# Sheet1.net
KiCad netlist of a schematic drawn in Altium Designer
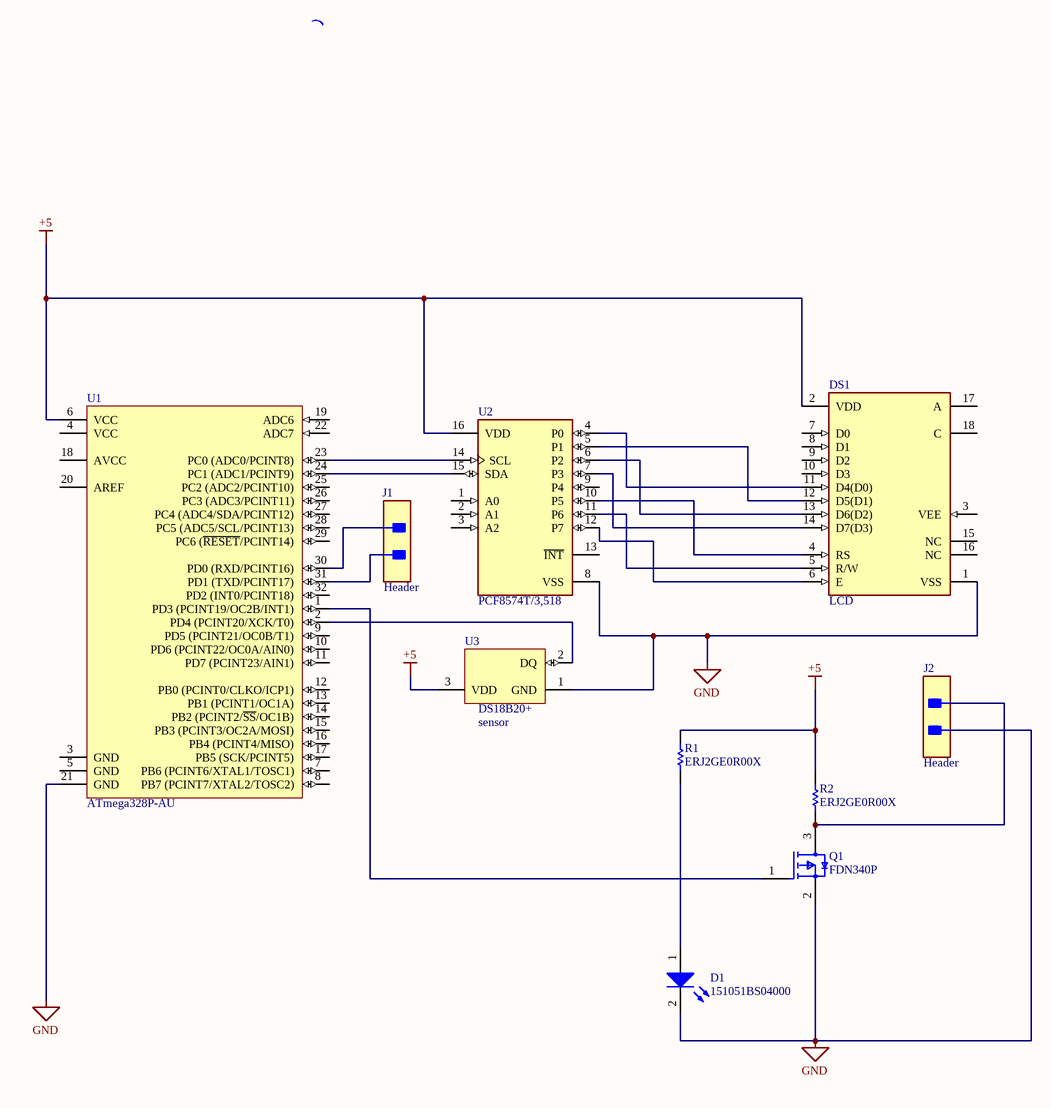
[diagram p0: Sheet1.SchDoc]

(export (version "E")
  (design (tool "Eeschema 10.0.6"))
  (components
    (comp (ref "D1")
      (value "151051BS04000")
      (footprint "WL-TMRC_D5.9H8.7")
      (libsource (lib "Altium Content Vault") (part "LED_Blue_1A-2K"))
    )
    (comp (ref "DS1")
      (value "LCD")
      (footprint "FP-EA_DIP162-DHNLED-MFG")
      (description "LCD MOD CHAR 2X16 Y/G BACKLIT")
      (fields
        (field (name "MANUFACTURER PART NUMBER") "EA DIP162-DHNLED")
        (field (name "MANUFACTURER") "Display Visions")
      )
      (libsource (lib "Altium Content Vault") (part "d15ad439837a3ed901fb7cfc26901aa"))
    )
    (comp (ref "J1")
      (value "Header")
      (footprint "FP-SYP-02T-1-MFG")
      (description "CONN PLUG HSNG 2POS 2.5MM RED")
      (libsource (lib "") (part "31f24ba94ab9d7f7090826e91f45e53_1"))
    )
    (comp (ref "J2")
      (value "Header")
      (footprint "FP-SYP-02T-1-MFG")
      (description "CONN PLUG HSNG 2POS 2.5MM RED")
      (libsource (lib "Altium Content Vault") (part "31f24ba94ab9d7f7090826e91f45e53"))
    )
    (comp (ref "Q1")
      (value "FDN340P")
      (footprint "FP-527AG-MFG")
      (description "MOSFET P-CH 20V 2A SSOT3")
      (libsource (lib "Altium Content Vault") (part "d23f43cc42f60b967b7caccf14518fd"))
    )
    (comp (ref "R1")
      (value "ERJ2GE0R00X")
      (footprint "RESC1005X40X25LL05T05")
      (description "Chip Resistor, 0 Ohm, 0.1 W, -55 to 155 degC, 0402 (1005 Metric), RoHS, Tape and Reel")
      (fields (field (name "MANUFACTURER") "Panasonic") (field (name "TOLERANCE") "5%"))
      (libsource (lib "Altium Content Vault") (part "RES-2"))
    )
    (comp (ref "R2")
      (value "ERJ2GE0R00X")
      (footprint "RESC1005X40X25LL05T05")
      (description "Chip Resistor, 0 Ohm, 0.1 W, -55 to 155 degC, 0402 (1005 Metric), RoHS, Tape and Reel")
      (fields (field (name "MANUFACTURER") "Panasonic") (field (name "TOLERANCE") "5%"))
      (libsource (lib "Altium Content Vault") (part "RES-2"))
    )
    (comp (ref "U1")
      (value "ATmega328P-AU")
      (footprint "32A_M")
      (libsource (lib "Altium Content Vault") (part "MC-8B-ATM48-SQ32"))
    )
    (comp (ref "U2")
      (value "PCF8574T/3,518")
      (footprint "FP-SOT162-1-MFG")
      (description "IC I/O EXPANDER I2C 8B 16SOIC")
      (fields
        (field (name "MANUFACTURER") "NXP Semiconductors")
        (field (name "OCTOPART") "https://octopart.com/pcf8574t%2F3%2C518-nxp+semiconductors-10470852")
      )
      (libsource (lib "Altium Content Vault") (part "f7fde53ce59de981fb0b266a4e103eb"))
    )
    (comp (ref "U3")
      (value "DS18B20+")
      (footprint "Q3+1")
      (libsource (lib "Altium Content Vault") (part "SEN-TEMP-DS1821-SIL3"))
    )
  )
  (nets
    (net (code "1") (name "+5") (class "Default")
      (node (ref "DS1") (pin "2") (pinfunction "VDD_2") (pintype "power_in"))
      (node (ref "R1") (pin "2") (pinfunction "2_2") (pintype "passive"))
      (node (ref "R2") (pin "2") (pinfunction "2_2") (pintype "passive"))
      (node (ref "U1") (pin "6") (pinfunction "VCC_6") (pintype "power_in"))
      (node (ref "U2") (pin "16") (pinfunction "VDD_16") (pintype "power_in"))
      (node (ref "U3") (pin "3") (pinfunction "VDD_3") (pintype "power_in"))
    )
    (net (code "2") (name "GND") (class "Default")
      (node (ref "D1") (pin "2") (pinfunction "K_2") (pintype "passive"))
      (node (ref "DS1") (pin "1") (pinfunction "VSS_1") (pintype "power_in"))
      (node (ref "Q1") (pin "2") (pinfunction "S_2") (pintype "passive"))
      (node (ref "U1") (pin "21") (pinfunction "GND_21") (pintype "power_in"))
      (node (ref "U2") (pin "8") (pinfunction "VSS_8") (pintype "power_in"))
      (node (ref "U3") (pin "1") (pinfunction "GND_1") (pintype "power_in"))
    )
    (net (code "3") (name "Net-(D1-A)") (class "Default")
      (node (ref "D1") (pin "1") (pinfunction "A_1") (pintype "passive"))
      (node (ref "R1") (pin "1") (pinfunction "1_1") (pintype "passive"))
    )
    (net (code "4") (name "Net-(DS1-D4(D0))") (class "Default")
      (node (ref "DS1") (pin "11") (pinfunction "D4(D0)_11") (pintype "input"))
      (node (ref "U2") (pin "4") (pinfunction "P0_4") (pintype "bidirectional"))
    )
    (net (code "5") (name "Net-(DS1-D5(D1))") (class "Default")
      (node (ref "DS1") (pin "12") (pinfunction "D5(D1)_12") (pintype "input"))
      (node (ref "U2") (pin "5") (pinfunction "P1_5") (pintype "bidirectional"))
    )
    (net (code "6") (name "Net-(DS1-D6(D2))") (class "Default")
      (node (ref "DS1") (pin "13") (pinfunction "D6(D2)_13") (pintype "input"))
      (node (ref "U2") (pin "6") (pinfunction "P2_6") (pintype "bidirectional"))
    )
    (net (code "7") (name "Net-(DS1-D7(D3))") (class "Default")
      (node (ref "DS1") (pin "14") (pinfunction "D7(D3)_14") (pintype "input"))
      (node (ref "U2") (pin "7") (pinfunction "P3_7") (pintype "bidirectional"))
    )
    (net (code "8") (name "Net-(DS1-E)") (class "Default")
      (node (ref "DS1") (pin "6") (pinfunction "E_6") (pintype "input"))
      (node (ref "U2") (pin "12") (pinfunction "P7_12") (pintype "bidirectional"))
    )
    (net (code "9") (name "Net-(DS1-RS)") (class "Default")
      (node (ref "DS1") (pin "4") (pinfunction "RS_4") (pintype "input"))
      (node (ref "U2") (pin "10") (pinfunction "P5_10") (pintype "bidirectional"))
    )
    (net (code "10") (name "Net-(DS1-R{slash}W)") (class "Default")
      (node (ref "DS1") (pin "5") (pinfunction "R/W_5") (pintype "input"))
      (node (ref "U2") (pin "11") (pinfunction "P6_11") (pintype "bidirectional"))
    )
    (net (code "11") (name "Net-(Q1-D)") (class "Default")
      (node (ref "Q1") (pin "3") (pinfunction "D_3") (pintype "passive"))
      (node (ref "R2") (pin "1") (pinfunction "1_1") (pintype "passive"))
    )
    (net (code "12") (name "Net-(Q1-G)") (class "Default")
      (node (ref "Q1") (pin "1") (pinfunction "G_1") (pintype "passive"))
      (node (ref "U1") (pin "1") (pinfunction "PD3_(PCINT19/OC2B/INT1)_1") (pintype "bidirectional"))
    )
    (net (code "13") (name "Net-(U1-PC0_(ADC0{slash}PCINT8))") (class "Default")
      (node (ref "U1") (pin "23") (pinfunction "PC0_(ADC0/PCINT8)_23") (pintype "bidirectional"))
      (node (ref "U2") (pin "14") (pinfunction "SCL_14") (pintype "input"))
    )
    (net (code "14") (name "Net-(U1-PC1_(ADC1{slash}PCINT9))") (class "Default")
      (node (ref "U1") (pin "24") (pinfunction "PC1_(ADC1/PCINT9)_24") (pintype "bidirectional"))
      (node (ref "U2") (pin "15") (pinfunction "SDA_15") (pintype "bidirectional"))
    )
    (net (code "15") (name "Net-(U1-PD4_(PCINT20{slash}XCK{slash}T0))") (class "Default")
      (node (ref "U1") (pin "2") (pinfunction "PD4_(PCINT20/XCK/T0)_2") (pintype "bidirectional"))
      (node (ref "U3") (pin "2") (pinfunction "DQ_2") (pintype "bidirectional"))
    )
    (net (code "16") (name "unconnected-(DS1-A-Pad17)") (class "Default")
      (node (ref "DS1") (pin "17") (pinfunction "A_17") (pintype "passive"))
    )
    (net (code "17") (name "unconnected-(DS1-C-Pad18)") (class "Default")
      (node (ref "DS1") (pin "18") (pinfunction "C_18") (pintype "passive"))
    )
    (net (code "18") (name "unconnected-(DS1-D0-Pad7)") (class "Default")
      (node (ref "DS1") (pin "7") (pinfunction "D0_7") (pintype "input"))
    )
    (net (code "19") (name "unconnected-(DS1-D1-Pad8)") (class "Default")
      (node (ref "DS1") (pin "8") (pinfunction "D1_8") (pintype "input"))
    )
    (net (code "20") (name "unconnected-(DS1-D2-Pad9)") (class "Default")
      (node (ref "DS1") (pin "9") (pinfunction "D2_9") (pintype "input"))
    )
    (net (code "21") (name "unconnected-(DS1-D3-Pad10)") (class "Default")
      (node (ref "DS1") (pin "10") (pinfunction "D3_10") (pintype "input"))
    )
    (net (code "22") (name "unconnected-(DS1-NC-Pad15)") (class "Default")
      (node (ref "DS1") (pin "15") (pinfunction "NC_15") (pintype "passive"))
    )
    (net (code "23") (name "unconnected-(DS1-NC-Pad16)") (class "Default")
      (node (ref "DS1") (pin "16") (pinfunction "NC_16") (pintype "passive"))
    )
    (net (code "24") (name "unconnected-(DS1-VEE-Pad3)") (class "Default")
      (node (ref "DS1") (pin "3") (pinfunction "VEE_3") (pintype "input"))
    )
    (net (code "25") (name "unconnected-(U1-ADC6-Pad19)") (class "Default")
      (node (ref "U1") (pin "19") (pinfunction "ADC6_19") (pintype "input"))
    )
    (net (code "26") (name "unconnected-(U1-ADC7-Pad22)") (class "Default")
      (node (ref "U1") (pin "22") (pinfunction "ADC7_22") (pintype "input"))
    )
    (net (code "27") (name "unconnected-(U1-AREF-Pad20)") (class "Default")
      (node (ref "U1") (pin "20") (pinfunction "AREF_20") (pintype "passive"))
    )
    (net (code "28") (name "unconnected-(U1-AVCC-Pad18)") (class "Default")
      (node (ref "U1") (pin "18") (pinfunction "AVCC_18") (pintype "power_in"))
    )
    (net (code "29") (name "unconnected-(U1-GND-Pad3)") (class "Default")
      (node (ref "U1") (pin "3") (pinfunction "GND_3") (pintype "power_in"))
    )
    (net (code "30") (name "unconnected-(U1-GND-Pad5)") (class "Default")
      (node (ref "U1") (pin "5") (pinfunction "GND_5") (pintype "power_in"))
    )
    (net (code "31") (name "unconnected-(U1-PB0_(PCINT0{slash}CLKO{slash}ICP1)-Pad12)") (class "Default")
      (node (ref "U1") (pin "12") (pinfunction "PB0_(PCINT0/CLKO/ICP1)_12") (pintype "bidirectional"))
    )
    (net (code "32") (name "unconnected-(U1-PB1_(PCINT1{slash}OC1A)-Pad13)") (class "Default")
      (node (ref "U1") (pin "13") (pinfunction "PB1_(PCINT1/OC1A)_13") (pintype "bidirectional"))
    )
    (net (code "33") (name "unconnected-(U1-PB2_(PCINT2{slash}~{SS}{slash}OC1B)-Pad14)") (class "Default")
      (node (ref "U1") (pin "14") (pinfunction "PB2_(PCINT2/~{SS}/OC1B)_14") (pintype "bidirectional"))
    )
    (net (code "34") (name "unconnected-(U1-PB3_(PCINT3{slash}OC2A{slash}MOSI)-Pad15)") (class "Default")
      (node (ref "U1") (pin "15") (pinfunction "PB3_(PCINT3/OC2A/MOSI)_15") (pintype "bidirectional"))
    )
    (net (code "35") (name "unconnected-(U1-PB4_(PCINT4{slash}MISO)-Pad16)") (class "Default")
      (node (ref "U1") (pin "16") (pinfunction "PB4_(PCINT4/MISO)_16") (pintype "bidirectional"))
    )
    (net (code "36") (name "unconnected-(U1-PB5_(SCK{slash}PCINT5)-Pad17)") (class "Default")
      (node (ref "U1") (pin "17") (pinfunction "PB5_(SCK/PCINT5)_17") (pintype "bidirectional"))
    )
    (net (code "37") (name "unconnected-(U1-PB6_(PCINT6{slash}XTAL1{slash}TOSC1)-Pad7)") (class "Default")
      (node (ref "U1") (pin "7") (pinfunction "PB6_(PCINT6/XTAL1/TOSC1)_7") (pintype "bidirectional"))
    )
    (net (code "38") (name "unconnected-(U1-PB7_(PCINT7{slash}XTAL2{slash}TOSC2)-Pad8)") (class "Default")
      (node (ref "U1") (pin "8") (pinfunction "PB7_(PCINT7/XTAL2/TOSC2)_8") (pintype "bidirectional"))
    )
    (net (code "39") (name "unconnected-(U1-PC2_(ADC2{slash}PCINT10)-Pad25)") (class "Default")
      (node (ref "U1") (pin "25") (pinfunction "PC2_(ADC2/PCINT10)_25") (pintype "bidirectional"))
    )
    (net (code "40") (name "unconnected-(U1-PC3_(ADC3{slash}PCINT11)-Pad26)") (class "Default")
      (node (ref "U1") (pin "26") (pinfunction "PC3_(ADC3/PCINT11)_26") (pintype "bidirectional"))
    )
    (net (code "41") (name "unconnected-(U1-PC4_(ADC4{slash}SDA{slash}PCINT12)-Pad27)") (class "Default")
      (node (ref "U1") (pin "27") (pinfunction "PC4_(ADC4/SDA/PCINT12)_27") (pintype "bidirectional"))
    )
    (net (code "42") (name "unconnected-(U1-PC5_(ADC5{slash}SCL{slash}PCINT13)-Pad28)") (class "Default")
      (node (ref "U1") (pin "28") (pinfunction "PC5_(ADC5/SCL/PCINT13)_28") (pintype "bidirectional"))
    )
    (net (code "43") (name "unconnected-(U1-PC6_(~{RESET}{slash}PCINT14)-Pad29)") (class "Default")
      (node (ref "U1") (pin "29") (pinfunction "PC6_(~{RESET}/PCINT14)_29") (pintype "bidirectional"))
    )
    (net (code "44") (name "unconnected-(U1-PD0_(RXD{slash}PCINT16)-Pad30)") (class "Default")
      (node (ref "U1") (pin "30") (pinfunction "PD0_(RXD/PCINT16)_30") (pintype "bidirectional"))
    )
    (net (code "45") (name "unconnected-(U1-PD1_(TXD{slash}PCINT17)-Pad31)") (class "Default")
      (node (ref "U1") (pin "31") (pinfunction "PD1_(TXD/PCINT17)_31") (pintype "bidirectional"))
    )
    (net (code "46") (name "unconnected-(U1-PD2_(INT0{slash}PCINT18)-Pad32)") (class "Default")
      (node (ref "U1") (pin "32") (pinfunction "PD2_(INT0/PCINT18)_32") (pintype "bidirectional"))
    )
    (net (code "47") (name "unconnected-(U1-PD5_(PCINT21{slash}OC0B{slash}T1)-Pad9)") (class "Default")
      (node (ref "U1") (pin "9") (pinfunction "PD5_(PCINT21/OC0B/T1)_9") (pintype "bidirectional"))
    )
    (net (code "48") (name "unconnected-(U1-PD6_(PCINT22{slash}OC0A{slash}AIN0)-Pad10)") (class "Default")
      (node (ref "U1") (pin "10") (pinfunction "PD6_(PCINT22/OC0A/AIN0)_10") (pintype "bidirectional"))
    )
    (net (code "49") (name "unconnected-(U1-PD7_(PCINT23{slash}AIN1)-Pad11)") (class "Default")
      (node (ref "U1") (pin "11") (pinfunction "PD7_(PCINT23/AIN1)_11") (pintype "bidirectional"))
    )
    (net (code "50") (name "unconnected-(U1-VCC-Pad4)") (class "Default")
      (node (ref "U1") (pin "4") (pinfunction "VCC_4") (pintype "power_in"))
    )
    (net (code "51") (name "unconnected-(U2-A0-Pad1)") (class "Default")
      (node (ref "U2") (pin "1") (pinfunction "A0_1") (pintype "input"))
    )
    (net (code "52") (name "unconnected-(U2-A1-Pad2)") (class "Default")
      (node (ref "U2") (pin "2") (pinfunction "A1_2") (pintype "input"))
    )
    (net (code "53") (name "unconnected-(U2-A2-Pad3)") (class "Default")
      (node (ref "U2") (pin "3") (pinfunction "A2_3") (pintype "input"))
    )
    (net (code "54") (name "unconnected-(U2-P4-Pad9)") (class "Default")
      (node (ref "U2") (pin "9") (pinfunction "P4_9") (pintype "bidirectional"))
    )
    (net (code "55") (name "unconnected-(U2-~{INT}-Pad13)") (class "Default")
      (node (ref "U2") (pin "13") (pinfunction "~{INT}_13") (pintype "open_collector"))
    )
  )
)
